# PD_Controller_TI.net
KiCad netlist of a schematic drawn in Altium Designer
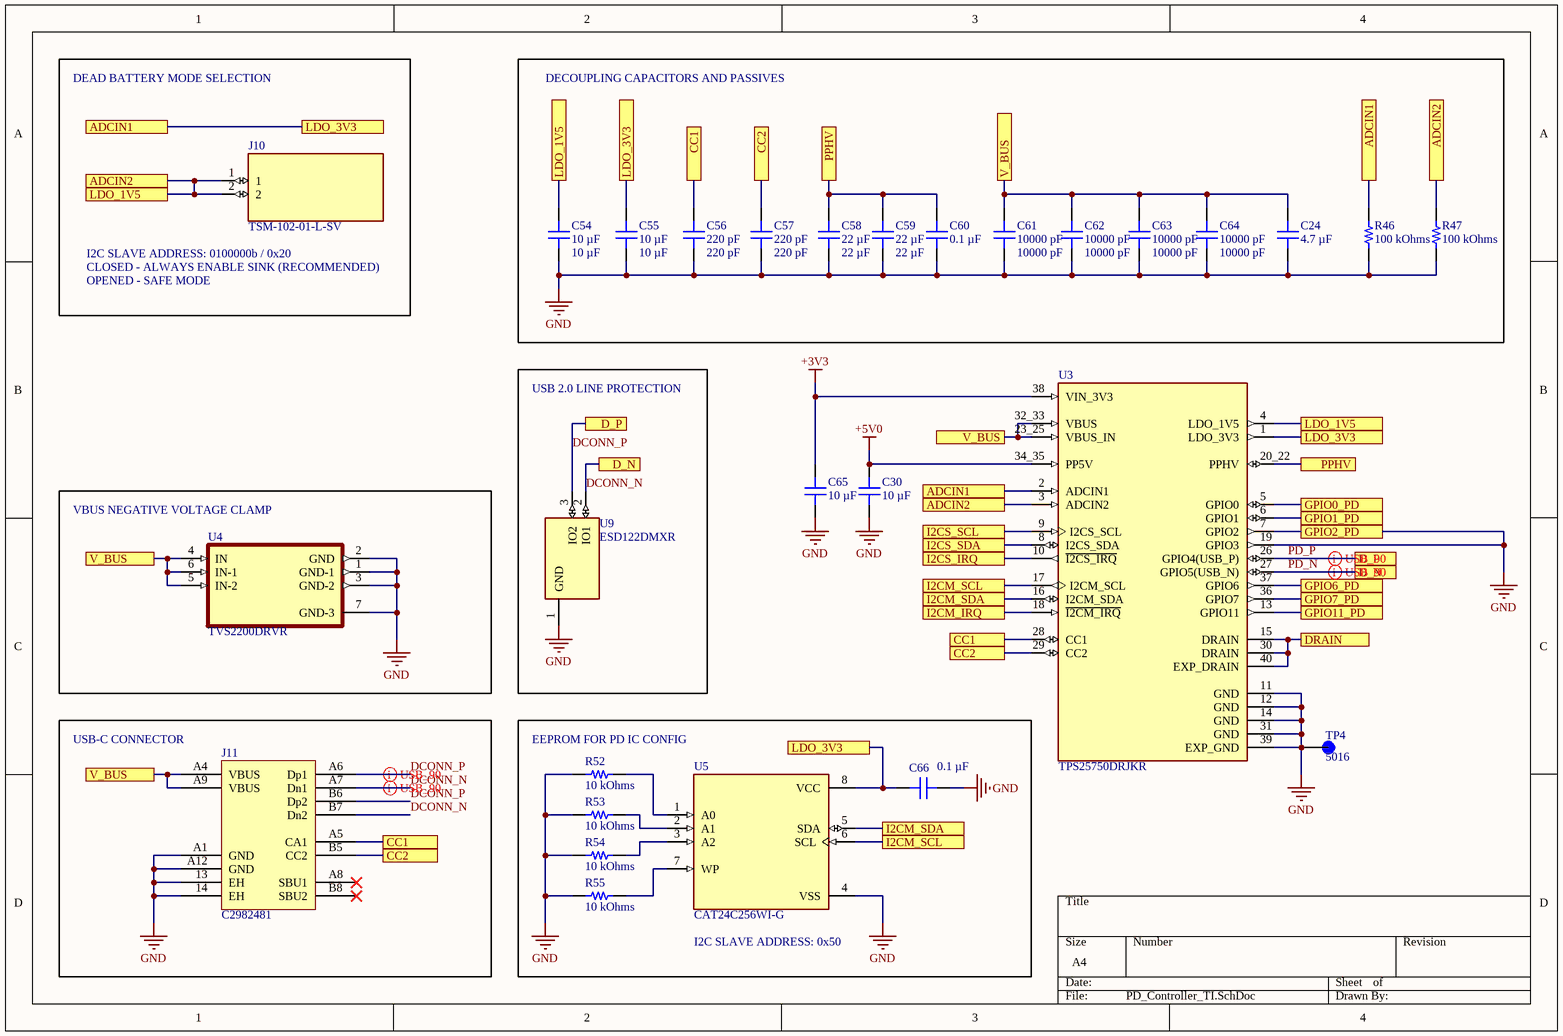
[diagram p0: PD_Controller_TI.SchDoc]

(export (version "E")
  (design (tool "Eeschema 10.0.6"))
  (components
    (comp (ref "C24")
      (value "4.7 µF")
      (footprint "CAP 0603_1608")
      (description "CAP CER 4.7UF 35V X5R 0603")
      (fields
        (field (name "PART NUMBER") "C1608X5R1V475K080AC")
        (field (name "MANUFACTURER") "TDK Corporation")
      )
      (libsource (lib "Celestial Altium Library - altium_library") (part "Capacitor"))
    )
    (comp (ref "C30")
      (value "10 µF")
      (footprint "CAP 0402_1005")
      (description "CAP CER 10UF 10V X5R 0402")
      (fields
        (field (name "PART NUMBER") "CL05A106MP8NUB8")
        (field (name "MANUFACTURER") "Samsung Electro-Mechanics")
      )
      (libsource (lib "Celestial Altium Library - altium_library") (part "Capacitor"))
    )
    (comp (ref "C54")
      (value "10 µF")
      (footprint "CAP 0402_1005")
      (description "CAP CER 10UF 10V X5R 0402")
      (fields
        (field (name "PART NUMBER") "CL05A106MP8NUB8")
        (field (name "ALTIUM_VALUE") "10 µF")
        (field (name "MANUFACTURER") "Samsung Electro-Mechanics")
      )
      (libsource (lib "Celestial Altium Library - altium_library") (part "Capacitor"))
    )
    (comp (ref "C55")
      (value "10 µF")
      (footprint "CAP 0402_1005")
      (description "CAP CER 10UF 10V X5R 0402")
      (fields
        (field (name "PART NUMBER") "CL05A106MP8NUB8")
        (field (name "ALTIUM_VALUE") "10 µF")
        (field (name "MANUFACTURER") "Samsung Electro-Mechanics")
      )
      (libsource (lib "Celestial Altium Library - altium_library") (part "Capacitor"))
    )
    (comp (ref "C56")
      (value "220 pF")
      (footprint "CAP 0402_1005")
      (description "CAP CER 220PF 16V X7R 0402")
      (fields
        (field (name "PART NUMBER") "885012205021")
        (field (name "ALTIUM_VALUE") "220 pF")
        (field (name "MANUFACTURER") "Würth Elektronik")
      )
      (libsource (lib "Celestial Altium Library - altium_library") (part "Capacitor"))
    )
    (comp (ref "C57")
      (value "220 pF")
      (footprint "CAP 0402_1005")
      (description "CAP CER 220PF 16V X7R 0402")
      (fields
        (field (name "PART NUMBER") "885012205021")
        (field (name "ALTIUM_VALUE") "220 pF")
        (field (name "MANUFACTURER") "Würth Elektronik")
      )
      (libsource (lib "Celestial Altium Library - altium_library") (part "Capacitor"))
    )
    (comp (ref "C58")
      (value "22 µF")
      (footprint "CAP 0805_2012")
      (description "CAP CER 22UF 35V X5R 0805")
      (fields
        (field (name "PART NUMBER") "C2012X5R1V226M125AC")
        (field (name "ALTIUM_VALUE") "22 µF")
        (field (name "MANUFACTURER") "TDK Corporation")
      )
      (libsource (lib "Celestial Altium Library - altium_library") (part "Capacitor"))
    )
    (comp (ref "C59")
      (value "22 µF")
      (footprint "CAP 0805_2012")
      (description "CAP CER 22UF 35V X5R 0805")
      (fields
        (field (name "PART NUMBER") "C2012X5R1V226M125AC")
        (field (name "ALTIUM_VALUE") "22 µF")
        (field (name "MANUFACTURER") "TDK Corporation")
      )
      (libsource (lib "Celestial Altium Library - altium_library") (part "Capacitor"))
    )
    (comp (ref "C60")
      (value "0.1 µF")
      (footprint "CAP 0402_1005")
      (description "CAP CER 0.1UF 6.3V X5R 0402")
      (fields (field (name "PART NUMBER") "885012105001") (field (name "MANUFACTURER") "Würth Elektronik"))
      (libsource (lib "Celestial Altium Library - altium_library") (part "Capacitor"))
    )
    (comp (ref "C61")
      (value "10000 pF")
      (footprint "CAP 0402_1005")
      (description "CAP CER 10000PF 35V X7R 0402")
      (fields
        (field (name "PART NUMBER") "CGA2B3X7R1V103M050BB")
        (field (name "ALTIUM_VALUE") "10000 pF")
        (field (name "MANUFACTURER") "TDK Corporation")
      )
      (libsource (lib "Celestial Altium Library - altium_library") (part "Capacitor"))
    )
    (comp (ref "C62")
      (value "10000 pF")
      (footprint "CAP 0402_1005")
      (description "CAP CER 10000PF 35V X7R 0402")
      (fields
        (field (name "PART NUMBER") "CGA2B3X7R1V103M050BB")
        (field (name "ALTIUM_VALUE") "10000 pF")
        (field (name "MANUFACTURER") "TDK Corporation")
      )
      (libsource (lib "Celestial Altium Library - altium_library") (part "Capacitor"))
    )
    (comp (ref "C63")
      (value "10000 pF")
      (footprint "CAP 0402_1005")
      (description "CAP CER 10000PF 35V X7R 0402")
      (fields
        (field (name "PART NUMBER") "CGA2B3X7R1V103M050BB")
        (field (name "ALTIUM_VALUE") "10000 pF")
        (field (name "MANUFACTURER") "TDK Corporation")
      )
      (libsource (lib "Celestial Altium Library - altium_library") (part "Capacitor"))
    )
    (comp (ref "C64")
      (value "10000 pF")
      (footprint "CAP 0402_1005")
      (description "CAP CER 10000PF 35V X7R 0402")
      (fields
        (field (name "PART NUMBER") "CGA2B3X7R1V103M050BB")
        (field (name "ALTIUM_VALUE") "10000 pF")
        (field (name "MANUFACTURER") "TDK Corporation")
      )
      (libsource (lib "Celestial Altium Library - altium_library") (part "Capacitor"))
    )
    (comp (ref "C65")
      (value "10 µF")
      (footprint "CAP 0402_1005")
      (description "CAP CER 10UF 10V X5R 0402")
      (fields
        (field (name "PART NUMBER") "CL05A106MP8NUB8")
        (field (name "MANUFACTURER") "Samsung Electro-Mechanics")
      )
      (libsource (lib "Celestial Altium Library - altium_library") (part "Capacitor"))
    )
    (comp (ref "C66")
      (value "0.1 µF")
      (footprint "CAP 0402_1005")
      (description "CAP CER 0.1UF 6.3V X5R 0402")
      (fields (field (name "PART NUMBER") "885012105001") (field (name "MANUFACTURER") "Würth Elektronik"))
      (libsource (lib "Celestial Altium Library - altium_library") (part "Capacitor"))
    )
    (comp (ref "J10")
      (value "TSM-102-01-L-SV")
      (footprint "TSM-102-01-L-SV-P-TR:TSM-102-01-L-SV")
      (fields (field (name "MF") "{'manufacturer': u'Samtec Inc.'}"))
      (libsource (lib "*") (part "TSM-102-01-L-SV"))
    )
    (comp (ref "J11")
      (value "C2982481")
      (footprint "GT-USB-7079A")
      (description "5A 1 Surface Mount 16 Female -55℃~+85℃ Type-C SMD USB Connectors ROHS C2982481")
      (libsource (lib "Schlib2") (part "GT-USB-7079A"))
    )
    (comp (ref "R46")
      (value "100 kOhms")
      (footprint "RES 0402_1005")
      (description "RES SMD 100K OHM 1% 1/16W 0402")
      (fields (field (name "PART NUMBER") "RT0402FRE07100KL") (field (name "MANUFACTURER") "Yageo"))
      (libsource (lib "Celestial Altium Library - altium_library") (part "Resistor"))
    )
    (comp (ref "R47")
      (value "100 kOhms")
      (footprint "RES 0402_1005")
      (description "RES SMD 100K OHM 1% 1/16W 0402")
      (fields (field (name "PART NUMBER") "RT0402FRE07100KL") (field (name "MANUFACTURER") "Yageo"))
      (libsource (lib "Celestial Altium Library - altium_library") (part "Resistor"))
    )
    (comp (ref "R52")
      (value "10 kOhms")
      (footprint "RES 0402_1005")
      (description "RES 10K OHM 5% 1/16W 0402")
      (fields (field (name "PART NUMBER") "RC0402JR-1310KL") (field (name "MANUFACTURER") "Yageo"))
      (libsource (lib "Celestial Altium Library - altium_library") (part "Resistor"))
    )
    (comp (ref "R53")
      (value "10 kOhms")
      (footprint "RES 0402_1005")
      (description "RES 10K OHM 5% 1/16W 0402")
      (fields (field (name "PART NUMBER") "RC0402JR-1310KL") (field (name "MANUFACTURER") "Yageo"))
      (libsource (lib "Celestial Altium Library - altium_library") (part "Resistor"))
    )
    (comp (ref "R54")
      (value "10 kOhms")
      (footprint "RES 0402_1005")
      (description "RES 10K OHM 5% 1/16W 0402")
      (fields (field (name "PART NUMBER") "RC0402JR-1310KL") (field (name "MANUFACTURER") "Yageo"))
      (libsource (lib "Celestial Altium Library - altium_library") (part "Resistor"))
    )
    (comp (ref "R55")
      (value "10 kOhms")
      (footprint "RES 0402_1005")
      (description "RES 10K OHM 5% 1/16W 0402")
      (fields (field (name "PART NUMBER") "RC0402JR-1310KL") (field (name "MANUFACTURER") "Yageo"))
      (libsource (lib "Celestial Altium Library - altium_library") (part "Resistor"))
    )
    (comp (ref "TP4")
      (value "5016")
      (footprint "5016:KEYSTONE_5016")
      (fields (field (name "MF") "{'manufacturer': u'Keystone Electronics'}"))
      (libsource (lib "*") (part "5016"))
    )
    (comp (ref "U3")
      (value "TPS25750DRJKR")
      (footprint "TPS25750DRJKR:IC_TPS25750DRJKR")
      (description "USB, Type-C Controller PMIC 38-WQFN (4x6)")
      (fields (field (name "MF") "{'manufacturer': u'Texas Instruments'}"))
      (libsource (lib "TPS25750DRJKR") (part "TPS25750DRJKR"))
    )
    (comp (ref "U4")
      (value "TVS2200DRVR")
      (footprint "TVS2200DRVR:SON65P200X200X80-7N")
      (fields (field (name "MF") "{'manufacturer': u'Texas Instruments'}"))
      (libsource (lib "*") (part "TVS2200DRVR"))
    )
    (comp (ref "U5")
      (value "CAT24C256WI-G")
      (footprint "CAT24C256WI-G:SOIC127P600X175-8N")
      (description "EEPROM Memory IC 256Kb (32K x 8) IÂ²C 1MHz 500ns 8-SOIC")
      (fields (field (name "MF") "{'manufacturer': u'ON Semiconductor'}"))
      (libsource (lib "*") (part "CAT24C256WI-G"))
    )
    (comp (ref "U9")
      (value "ESD122DMXR")
      (footprint "ESD122DMXR:IC_ESD122DMXR")
      (description "2-channel ESD protection diode for USB Type-C and HDMI 2.0 3-X2SON -40 to 125")
      (fields (field (name "MF") "{'manufacturer': u'Texas Instruments'}"))
      (libsource (lib "*") (part "ESD122DMXR"))
    )
  )
  (nets
    (net (code "1") (name "+3V3") (class "Default")
      (node (ref "C65") (pin "1") (pinfunction "1_1") (pintype "passive"))
      (node (ref "U3") (pin "38") (pinfunction "VIN_3V3_38") (pintype "input"))
    )
    (net (code "2") (name "+5V0") (class "Default")
      (node (ref "C30") (pin "1") (pinfunction "1_1") (pintype "passive"))
      (node (ref "U3") (pin "34_35") (pinfunction "PP5V_34_35") (pintype "input"))
    )
    (net (code "3") (name "/ADCIN1") (class "Default")
      (node (ref "C55") (pin "2") (pinfunction "2_2") (pintype "passive"))
      (node (ref "C66") (pin "2") (pinfunction "2_2") (pintype "passive"))
      (node (ref "R46") (pin "2") (pinfunction "2_2") (pintype "passive"))
      (node (ref "U3") (pin "1") (pinfunction "LDO_3V3_1") (pintype "output"))
      (node (ref "U3") (pin "2") (pinfunction "ADCIN1_2") (pintype "input"))
      (node (ref "U5") (pin "8") (pinfunction "VCC_8") (pintype "power_in"))
    )
    (net (code "4") (name "/ADCIN2") (class "Default")
      (node (ref "C54") (pin "2") (pinfunction "2_2") (pintype "passive"))
      (node (ref "J10") (pin "1") (pinfunction "1_1") (pintype "bidirectional"))
      (node (ref "J10") (pin "2") (pinfunction "2_2") (pintype "bidirectional"))
      (node (ref "R47") (pin "2") (pinfunction "2_2") (pintype "passive"))
      (node (ref "U3") (pin "3") (pinfunction "ADCIN2_3") (pintype "input"))
      (node (ref "U3") (pin "4") (pinfunction "LDO_1V5_4") (pintype "output"))
    )
    (net (code "5") (name "/CC1") (class "Default")
      (node (ref "C56") (pin "1") (pinfunction "1_1") (pintype "passive"))
      (node (ref "J11") (pin "A5") (pinfunction "CA1_A5") (pintype "passive"))
      (node (ref "U3") (pin "28") (pinfunction "CC1_28") (pintype "bidirectional"))
    )
    (net (code "6") (name "/CC2") (class "Default")
      (node (ref "C57") (pin "1") (pinfunction "1_1") (pintype "passive"))
      (node (ref "J11") (pin "B5") (pinfunction "CC2_B5") (pintype "passive"))
      (node (ref "U3") (pin "29") (pinfunction "CC2_29") (pintype "bidirectional"))
    )
    (net (code "7") (name "/DCONN_N") (class "Default")
      (node (ref "J11") (pin "A7") (pinfunction "Dn1_A7") (pintype "passive"))
      (node (ref "J11") (pin "B7") (pinfunction "Dn2_B7") (pintype "passive"))
      (node (ref "U3") (pin "27") (pinfunction "GPIO5(USB_N)_27") (pintype "bidirectional"))
      (node (ref "U9") (pin "2") (pinfunction "IO1_2") (pintype "bidirectional"))
    )
    (net (code "8") (name "/DCONN_P") (class "Default")
      (node (ref "J11") (pin "A6") (pinfunction "Dp1_A6") (pintype "passive"))
      (node (ref "J11") (pin "B6") (pinfunction "Dp2_B6") (pintype "passive"))
      (node (ref "U3") (pin "26") (pinfunction "GPIO4(USB_P)_26") (pintype "bidirectional"))
      (node (ref "U9") (pin "3") (pinfunction "IO2_3") (pintype "bidirectional"))
    )
    (net (code "9") (name "/DRAIN") (class "Default")
      (node (ref "U3") (pin "15") (pinfunction "DRAIN_15") (pintype "passive"))
      (node (ref "U3") (pin "30") (pinfunction "DRAIN_30") (pintype "passive"))
      (node (ref "U3") (pin "40") (pinfunction "EXP_DRAIN_40") (pintype "passive"))
    )
    (net (code "10") (name "/GPIO0_PD") (class "Default")
      (node (ref "U3") (pin "5") (pinfunction "GPIO0_5") (pintype "bidirectional"))
    )
    (net (code "11") (name "/GPIO1_PD") (class "Default")
      (node (ref "U3") (pin "6") (pinfunction "GPIO1_6") (pintype "bidirectional"))
    )
    (net (code "12") (name "/GPIO6_PD") (class "Default")
      (node (ref "U3") (pin "37") (pinfunction "GPIO6_37") (pintype "output"))
    )
    (net (code "13") (name "/GPIO7_PD") (class "Default")
      (node (ref "U3") (pin "36") (pinfunction "GPIO7_36") (pintype "output"))
    )
    (net (code "14") (name "/GPIO11_PD") (class "Default")
      (node (ref "U3") (pin "13") (pinfunction "GPIO11_13") (pintype "output"))
    )
    (net (code "15") (name "/I2CM_IRQ") (class "Default")
      (node (ref "U3") (pin "18") (pinfunction "~{I2CM_IRQ}_18") (pintype "input"))
    )
    (net (code "16") (name "/I2CM_SCL") (class "Default")
      (node (ref "U3") (pin "17") (pinfunction "I2CM_SCL_17") (pintype "output"))
      (node (ref "U5") (pin "6") (pinfunction "SCL_6") (pintype "input"))
    )
    (net (code "17") (name "/I2CM_SDA") (class "Default")
      (node (ref "U3") (pin "16") (pinfunction "I2CM_SDA_16") (pintype "bidirectional"))
      (node (ref "U5") (pin "5") (pinfunction "SDA_5") (pintype "bidirectional"))
    )
    (net (code "18") (name "/I2CS_IRQ") (class "Default")
      (node (ref "U3") (pin "10") (pinfunction "~{I2CS_IRQ}_10") (pintype "output"))
    )
    (net (code "19") (name "/I2CS_SCL") (class "Default")
      (node (ref "U3") (pin "9") (pinfunction "I2CS_SCL_9") (pintype "input"))
    )
    (net (code "20") (name "/I2CS_SDA") (class "Default")
      (node (ref "U3") (pin "8") (pinfunction "I2CS_SDA_8") (pintype "bidirectional"))
    )
    (net (code "21") (name "/PPHV") (class "Default")
      (node (ref "C58") (pin "2") (pinfunction "2_2") (pintype "passive"))
      (node (ref "C59") (pin "2") (pinfunction "2_2") (pintype "passive"))
      (node (ref "C60") (pin "1") (pinfunction "1_1") (pintype "passive"))
      (node (ref "U3") (pin "20_22") (pinfunction "PPHV_20_22") (pintype "bidirectional"))
    )
    (net (code "22") (name "/V_BUS") (class "Default")
      (node (ref "C24") (pin "2") (pinfunction "2_2") (pintype "passive"))
      (node (ref "C61") (pin "2") (pinfunction "2_2") (pintype "passive"))
      (node (ref "C62") (pin "2") (pinfunction "2_2") (pintype "passive"))
      (node (ref "C63") (pin "2") (pinfunction "2_2") (pintype "passive"))
      (node (ref "C64") (pin "2") (pinfunction "2_2") (pintype "passive"))
      (node (ref "J11") (pin "A4") (pinfunction "VBUS_A4") (pintype "passive"))
      (node (ref "J11") (pin "A9") (pinfunction "VBUS_A9") (pintype "passive"))
      (node (ref "U3") (pin "23_25") (pinfunction "VBUS_IN_23_25") (pintype "input"))
      (node (ref "U3") (pin "32_33") (pinfunction "VBUS_32_33") (pintype "input"))
      (node (ref "U4") (pin "4") (pinfunction "IN_4") (pintype "input"))
      (node (ref "U4") (pin "5") (pinfunction "IN-2_5") (pintype "input"))
      (node (ref "U4") (pin "6") (pinfunction "IN-1_6") (pintype "input"))
    )
    (net (code "23") (name "GND") (class "Default")
      (node (ref "C24") (pin "1") (pinfunction "1_1") (pintype "passive"))
      (node (ref "C30") (pin "2") (pinfunction "2_2") (pintype "passive"))
      (node (ref "C54") (pin "1") (pinfunction "1_1") (pintype "passive"))
      (node (ref "C55") (pin "1") (pinfunction "1_1") (pintype "passive"))
      (node (ref "C56") (pin "2") (pinfunction "2_2") (pintype "passive"))
      (node (ref "C57") (pin "2") (pinfunction "2_2") (pintype "passive"))
      (node (ref "C58") (pin "1") (pinfunction "1_1") (pintype "passive"))
      (node (ref "C59") (pin "1") (pinfunction "1_1") (pintype "passive"))
      (node (ref "C60") (pin "2") (pinfunction "2_2") (pintype "passive"))
      (node (ref "C61") (pin "1") (pinfunction "1_1") (pintype "passive"))
      (node (ref "C62") (pin "1") (pinfunction "1_1") (pintype "passive"))
      (node (ref "C63") (pin "1") (pinfunction "1_1") (pintype "passive"))
      (node (ref "C64") (pin "1") (pinfunction "1_1") (pintype "passive"))
      (node (ref "C65") (pin "2") (pinfunction "2_2") (pintype "passive"))
      (node (ref "C66") (pin "1") (pinfunction "1_1") (pintype "passive"))
      (node (ref "J11") (pin "13") (pinfunction "EH_13") (pintype "passive"))
      (node (ref "J11") (pin "14") (pinfunction "EH_14") (pintype "passive"))
      (node (ref "J11") (pin "A1") (pinfunction "GND_A1") (pintype "passive"))
      (node (ref "J11") (pin "A12") (pinfunction "GND_A12") (pintype "passive"))
      (node (ref "R46") (pin "1") (pinfunction "1_1") (pintype "passive"))
      (node (ref "R47") (pin "1") (pinfunction "1_1") (pintype "passive"))
      (node (ref "R52") (pin "2") (pinfunction "2_2") (pintype "passive"))
      (node (ref "R53") (pin "2") (pinfunction "2_2") (pintype "passive"))
      (node (ref "R54") (pin "2") (pinfunction "2_2") (pintype "passive"))
      (node (ref "R55") (pin "2") (pinfunction "2_2") (pintype "passive"))
      (node (ref "TP4") (pin "TP") (pinfunction "TP_TP") (pintype "passive"))
      (node (ref "U3") (pin "11") (pinfunction "GND_11") (pintype "power_in"))
      (node (ref "U3") (pin "12") (pinfunction "GND_12") (pintype "power_in"))
      (node (ref "U3") (pin "14") (pinfunction "GND_14") (pintype "power_in"))
      (node (ref "U3") (pin "19") (pinfunction "GPIO3_19") (pintype "output"))
      (node (ref "U3") (pin "31") (pinfunction "GND_31") (pintype "power_in"))
      (node (ref "U3") (pin "39") (pinfunction "EXP_GND_39") (pintype "power_in"))
      (node (ref "U3") (pin "7") (pinfunction "GPIO2_7") (pintype "output"))
      (node (ref "U4") (pin "1") (pinfunction "GND-1_1") (pintype "output"))
      (node (ref "U4") (pin "2") (pinfunction "GND_2") (pintype "output"))
      (node (ref "U4") (pin "3") (pinfunction "GND-2_3") (pintype "output"))
      (node (ref "U4") (pin "7") (pinfunction "GND-3_7") (pintype "power_in"))
      (node (ref "U5") (pin "4") (pinfunction "VSS_4") (pintype "power_in"))
      (node (ref "U9") (pin "1") (pinfunction "GND_1") (pintype "power_in"))
    )
    (net (code "24") (name "Net-(U5-A0)") (class "Default")
      (node (ref "R52") (pin "1") (pinfunction "1_1") (pintype "passive"))
      (node (ref "U5") (pin "1") (pinfunction "A0_1") (pintype "input"))
    )
    (net (code "25") (name "Net-(U5-A1)") (class "Default")
      (node (ref "R53") (pin "1") (pinfunction "1_1") (pintype "passive"))
      (node (ref "U5") (pin "2") (pinfunction "A1_2") (pintype "input"))
    )
    (net (code "26") (name "Net-(U5-A2)") (class "Default")
      (node (ref "R54") (pin "1") (pinfunction "1_1") (pintype "passive"))
      (node (ref "U5") (pin "3") (pinfunction "A2_3") (pintype "input"))
    )
    (net (code "27") (name "Net-(U5-WP)") (class "Default")
      (node (ref "R55") (pin "1") (pinfunction "1_1") (pintype "passive"))
      (node (ref "U5") (pin "7") (pinfunction "WP_7") (pintype "input"))
    )
    (net (code "28") (name "unconnected-(J11-SBU1-PadA8)") (class "Default")
      (node (ref "J11") (pin "A8") (pinfunction "SBU1_A8") (pintype "passive+no_connect"))
    )
    (net (code "29") (name "unconnected-(J11-SBU2-PadB8)") (class "Default")
      (node (ref "J11") (pin "B8") (pinfunction "SBU2_B8") (pintype "passive+no_connect"))
    )
  )
)
